# MicroTeleinfo-V1_0.net
KiCad netlist of a schematic drawn in EAGLE
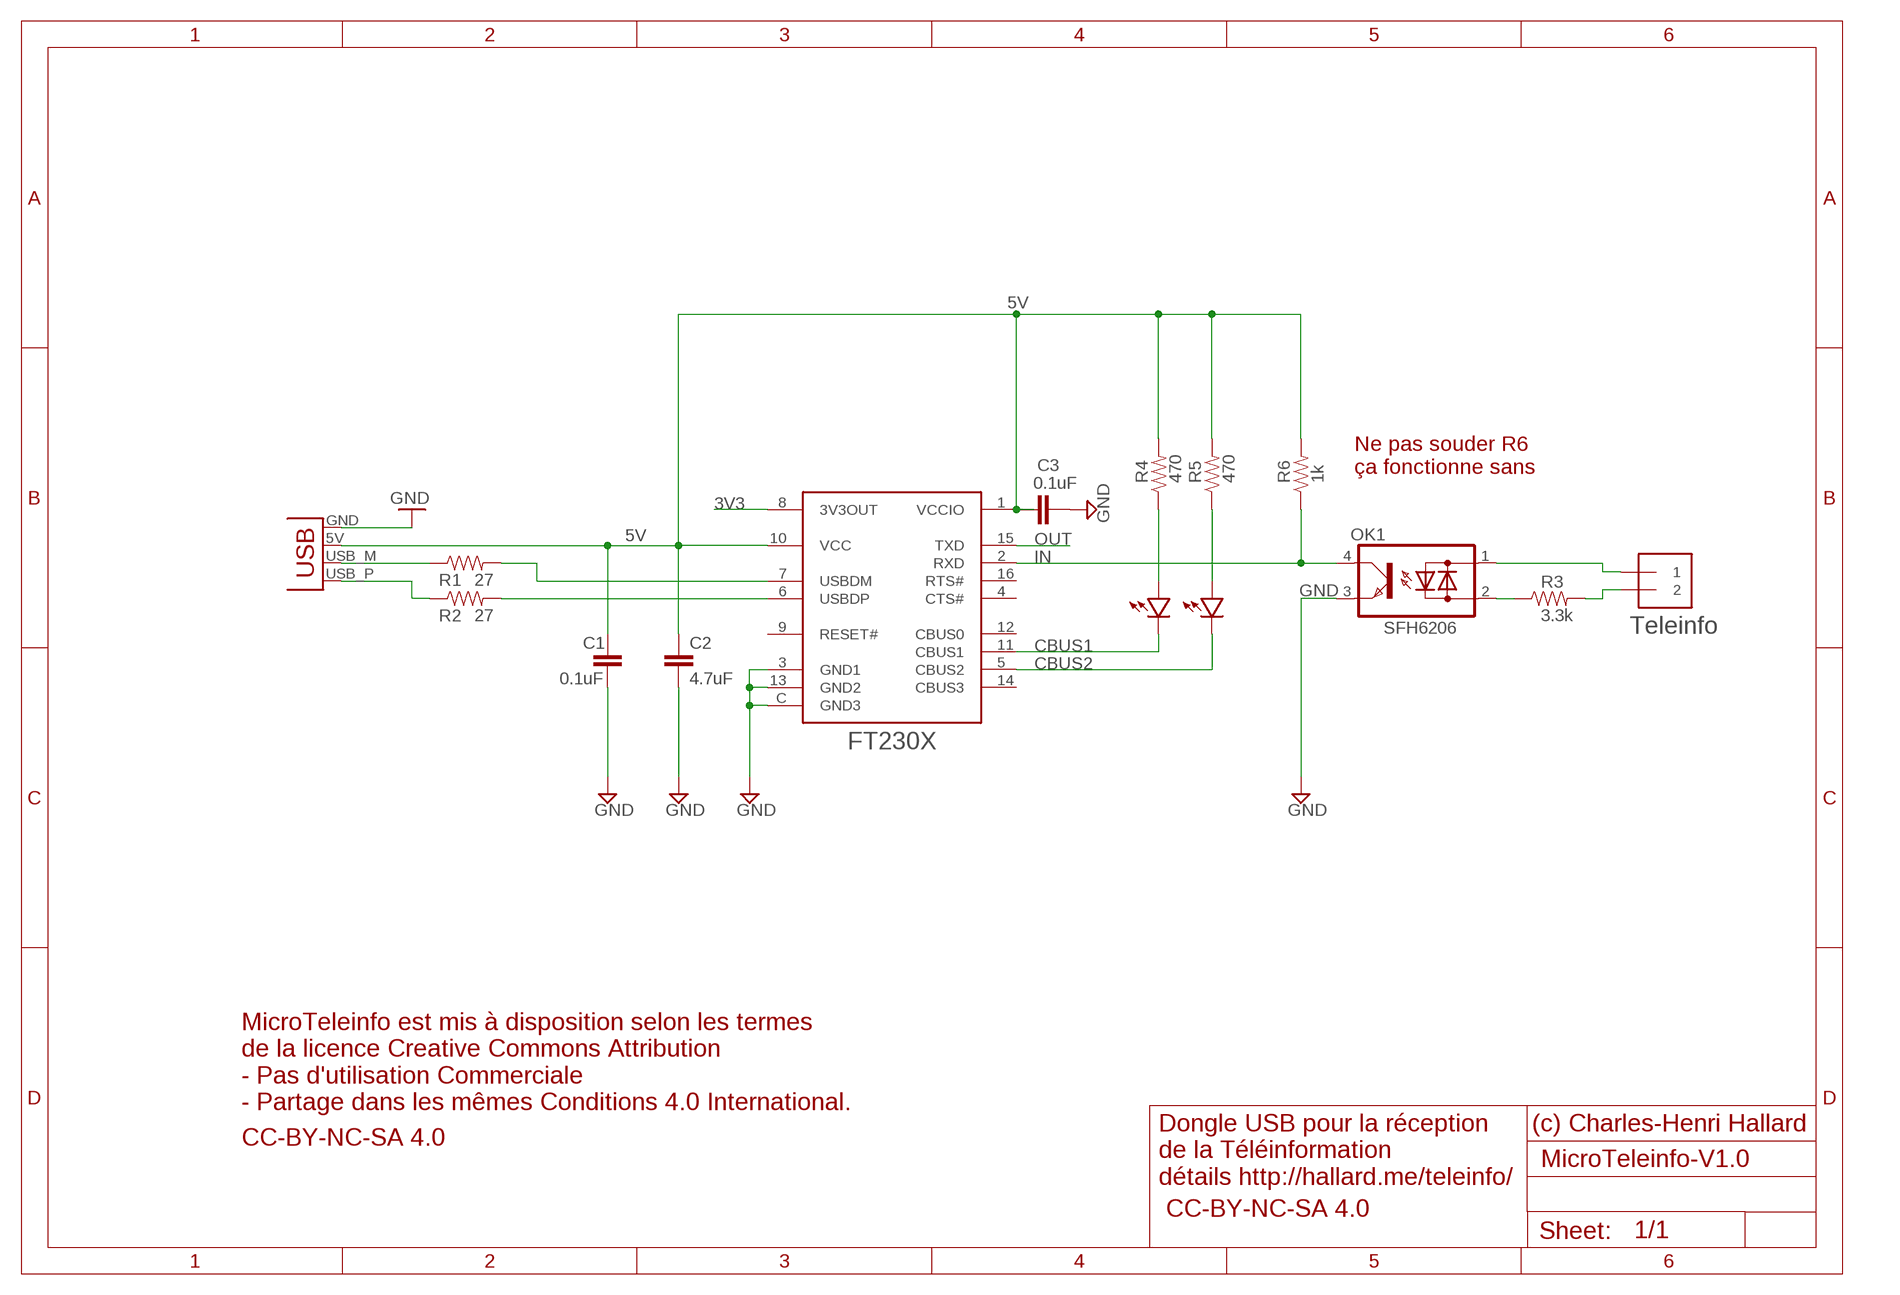
[diagram p0: schematic, sheet 1]

(export (version "E")
  (design (tool "Eeschema 10.0.6"))
  (components
    (comp (ref "C1")
      (value "0.1uF")
      (footprint "eagle-import:0603-CAP")
      (libsource (lib "eagle-import") (part "CAP0603-CAP"))
    )
    (comp (ref "C2")
      (value "4.7uF")
      (footprint "eagle-import:0805-CAP")
      (libsource (lib "eagle-import") (part "_c2h_CAP0805-CAP"))
    )
    (comp (ref "C3")
      (value "0.1uF")
      (footprint "eagle-import:0603-CAP")
      (libsource (lib "eagle-import") (part "CAP0603-CAP"))
    )
    (comp (ref "FT230X")
      (value "SERIAL_FT230XQ")
      (footprint "eagle-import:SERIAL_QFN4X4-16")
      (libsource (lib "eagle-import") (part "SERIAL_FT230XQ"))
    )
    (comp (ref "LED1")
      (value "Green")
      (footprint "eagle-import:0805-LED")
      (libsource (lib "eagle-import") (part "LED0805"))
    )
    (comp (ref "LED2")
      (value "Red")
      (footprint "eagle-import:0805-LED")
      (libsource (lib "eagle-import") (part "LED0805"))
    )
    (comp (ref "OK1")
      (value "SFH6206")
      (footprint "eagle-import:DIL4-SMD")
      (fields (field (name "MF") "VISHAY/TELEFUNKEN") (field (name "MPN") "SFH6206-3"))
      (libsource (lib "eagle-import") (part "SFH6206"))
    )
    (comp (ref "R1")
      (value "27")
      (footprint "eagle-import:0603-RES")
      (libsource (lib "eagle-import") (part "RESISTOR0603-RES"))
    )
    (comp (ref "R2")
      (value "27")
      (footprint "eagle-import:0603-RES")
      (libsource (lib "eagle-import") (part "RESISTOR0603-RES"))
    )
    (comp (ref "R3")
      (value "3.3k")
      (footprint "eagle-import:0805-RES")
      (libsource (lib "eagle-import") (part "_c2h_RESISTOR0805-RES"))
    )
    (comp (ref "R4")
      (value "470")
      (footprint "eagle-import:0603-RES")
      (libsource (lib "eagle-import") (part "RESISTOR0603-RES"))
    )
    (comp (ref "R5")
      (value "470")
      (footprint "eagle-import:0603-RES")
      (libsource (lib "eagle-import") (part "RESISTOR0603-RES"))
    )
    (comp (ref "R6")
      (value "1k")
      (footprint "eagle-import:0603-RES")
      (libsource (lib "eagle-import") (part "RESISTOR0603-RES"))
    )
    (comp (ref "TELEINFO")
      (value "1X2-3.5MM")
      (footprint "eagle-import:1X2-3.5MM")
      (libsource (lib "eagle-import") (part "1X2-3.5MM"))
    )
    (comp (ref "X1")
      (value "USBPCB")
      (footprint "eagle-import:USB-A-PCB")
      (libsource (lib "eagle-import") (part "USBPCB"))
    )
  )
  (nets
    (net (code "1") (name "/3V3") (class "Default")
      (node (ref "FT230X") (pin "8") (pinfunction "3V3OUT_8") (pintype "output"))
    )
    (net (code "2") (name "/5V") (class "Default")
      (node (ref "C1") (pin "1") (pinfunction "1_1") (pintype "passive"))
      (node (ref "C2") (pin "1") (pinfunction "1_1") (pintype "passive"))
      (node (ref "C3") (pin "1") (pinfunction "1_1") (pintype "passive"))
      (node (ref "FT230X") (pin "1") (pinfunction "VCCIO_1") (pintype "input"))
      (node (ref "FT230X") (pin "10") (pinfunction "VCC_10") (pintype "power_in"))
      (node (ref "R4") (pin "2") (pinfunction "2_2") (pintype "passive"))
      (node (ref "R5") (pin "2") (pinfunction "2_2") (pintype "passive"))
      (node (ref "R6") (pin "2") (pinfunction "2_2") (pintype "passive"))
      (node (ref "X1") (pin "5V") (pinfunction "VBUS_5V") (pintype "bidirectional"))
    )
    (net (code "3") (name "/CBUS1") (class "Default")
      (node (ref "FT230X") (pin "11") (pinfunction "CBUS1_11") (pintype "bidirectional"))
      (node (ref "LED1") (pin "MINUS") (pinfunction "MINUS_MINUS") (pintype "passive"))
    )
    (net (code "4") (name "/CBUS2") (class "Default")
      (node (ref "FT230X") (pin "5") (pinfunction "CBUS2_5") (pintype "bidirectional"))
      (node (ref "LED2") (pin "MINUS") (pinfunction "MINUS_MINUS") (pintype "passive"))
    )
    (net (code "5") (name "/IN") (class "Default")
      (node (ref "FT230X") (pin "2") (pinfunction "RXD_2") (pintype "input"))
      (node (ref "OK1") (pin "4") (pinfunction "C_4") (pintype "passive"))
      (node (ref "R6") (pin "1") (pinfunction "1_1") (pintype "passive"))
    )
    (net (code "6") (name "/OUT") (class "Default")
      (node (ref "FT230X") (pin "15") (pinfunction "TXD_15") (pintype "output"))
    )
    (net (code "7") (name "GND") (class "Default")
      (node (ref "C1") (pin "2") (pinfunction "2_2") (pintype "passive"))
      (node (ref "C2") (pin "2") (pinfunction "2_2") (pintype "passive"))
      (node (ref "C3") (pin "2") (pinfunction "2_2") (pintype "passive"))
      (node (ref "FT230X") (pin "13") (pinfunction "GND2_13") (pintype "power_in"))
      (node (ref "FT230X") (pin "3") (pinfunction "GND1_3") (pintype "power_in"))
      (node (ref "FT230X") (pin "C") (pinfunction "GND3_C") (pintype "power_in"))
      (node (ref "OK1") (pin "3") (pinfunction "E_3") (pintype "passive"))
      (node (ref "X1") (pin "GND") (pinfunction "GND_GND") (pintype "bidirectional"))
    )
    (net (code "8") (name "Net-(FT230X-USBDM)") (class "Default")
      (node (ref "FT230X") (pin "7") (pinfunction "USBDM_7") (pintype "bidirectional"))
      (node (ref "R1") (pin "2") (pinfunction "2_2") (pintype "passive"))
    )
    (net (code "9") (name "Net-(FT230X-USBDP)") (class "Default")
      (node (ref "FT230X") (pin "6") (pinfunction "USBDP_6") (pintype "bidirectional"))
      (node (ref "R2") (pin "2") (pinfunction "2_2") (pintype "passive"))
    )
    (net (code "10") (name "Net-(LED1-PadPLUS)") (class "Default")
      (node (ref "LED1") (pin "PLUS") (pinfunction "PLUS_PLUS") (pintype "passive"))
      (node (ref "R4") (pin "1") (pinfunction "1_1") (pintype "passive"))
    )
    (net (code "11") (name "Net-(LED2-PadPLUS)") (class "Default")
      (node (ref "LED2") (pin "PLUS") (pinfunction "PLUS_PLUS") (pintype "passive"))
      (node (ref "R5") (pin "1") (pinfunction "1_1") (pintype "passive"))
    )
    (net (code "12") (name "Net-(OK1-AC1)") (class "Default")
      (node (ref "OK1") (pin "1") (pinfunction "AC1_1") (pintype "passive"))
      (node (ref "TELEINFO") (pin "1") (pinfunction "1_1") (pintype "passive"))
    )
    (net (code "13") (name "Net-(OK1-AC2)") (class "Default")
      (node (ref "OK1") (pin "2") (pinfunction "AC2_2") (pintype "passive"))
      (node (ref "R3") (pin "1") (pinfunction "1_1") (pintype "passive"))
    )
    (net (code "14") (name "Net-(R3-Pad2)") (class "Default")
      (node (ref "R3") (pin "2") (pinfunction "2_2") (pintype "passive"))
      (node (ref "TELEINFO") (pin "2") (pinfunction "2_2") (pintype "passive"))
    )
    (net (code "15") (name "Net-(X1-D+)") (class "Default")
      (node (ref "R2") (pin "1") (pinfunction "1_1") (pintype "passive"))
      (node (ref "X1") (pin "USB_P") (pinfunction "D+_USB_P") (pintype "bidirectional"))
    )
    (net (code "16") (name "Net-(X1-D-)") (class "Default")
      (node (ref "R1") (pin "1") (pinfunction "1_1") (pintype "passive"))
      (node (ref "X1") (pin "USB_M") (pinfunction "D-_USB_M") (pintype "bidirectional"))
    )
    (net (code "17") (name "unconnected-(FT230X-CBUS0-Pad12)") (class "Default")
      (node (ref "FT230X") (pin "12") (pinfunction "CBUS0_12") (pintype "bidirectional"))
    )
    (net (code "18") (name "unconnected-(FT230X-CBUS3-Pad14)") (class "Default")
      (node (ref "FT230X") (pin "14") (pinfunction "CBUS3_14") (pintype "bidirectional"))
    )
    (net (code "19") (name "unconnected-(FT230X-CTS#-Pad4)") (class "Default")
      (node (ref "FT230X") (pin "4") (pinfunction "CTS#_4") (pintype "bidirectional"))
    )
    (net (code "20") (name "unconnected-(FT230X-RESET#-Pad9)") (class "Default")
      (node (ref "FT230X") (pin "9") (pinfunction "RESET#_9") (pintype "input"))
    )
    (net (code "21") (name "unconnected-(FT230X-RTS#-Pad16)") (class "Default")
      (node (ref "FT230X") (pin "16") (pinfunction "RTS#_16") (pintype "bidirectional"))
    )
  )
)
